# 5_RK3588_OSC_PLL_PMUIO1.net
KiCad netlist of a schematic drawn in Altium Designer
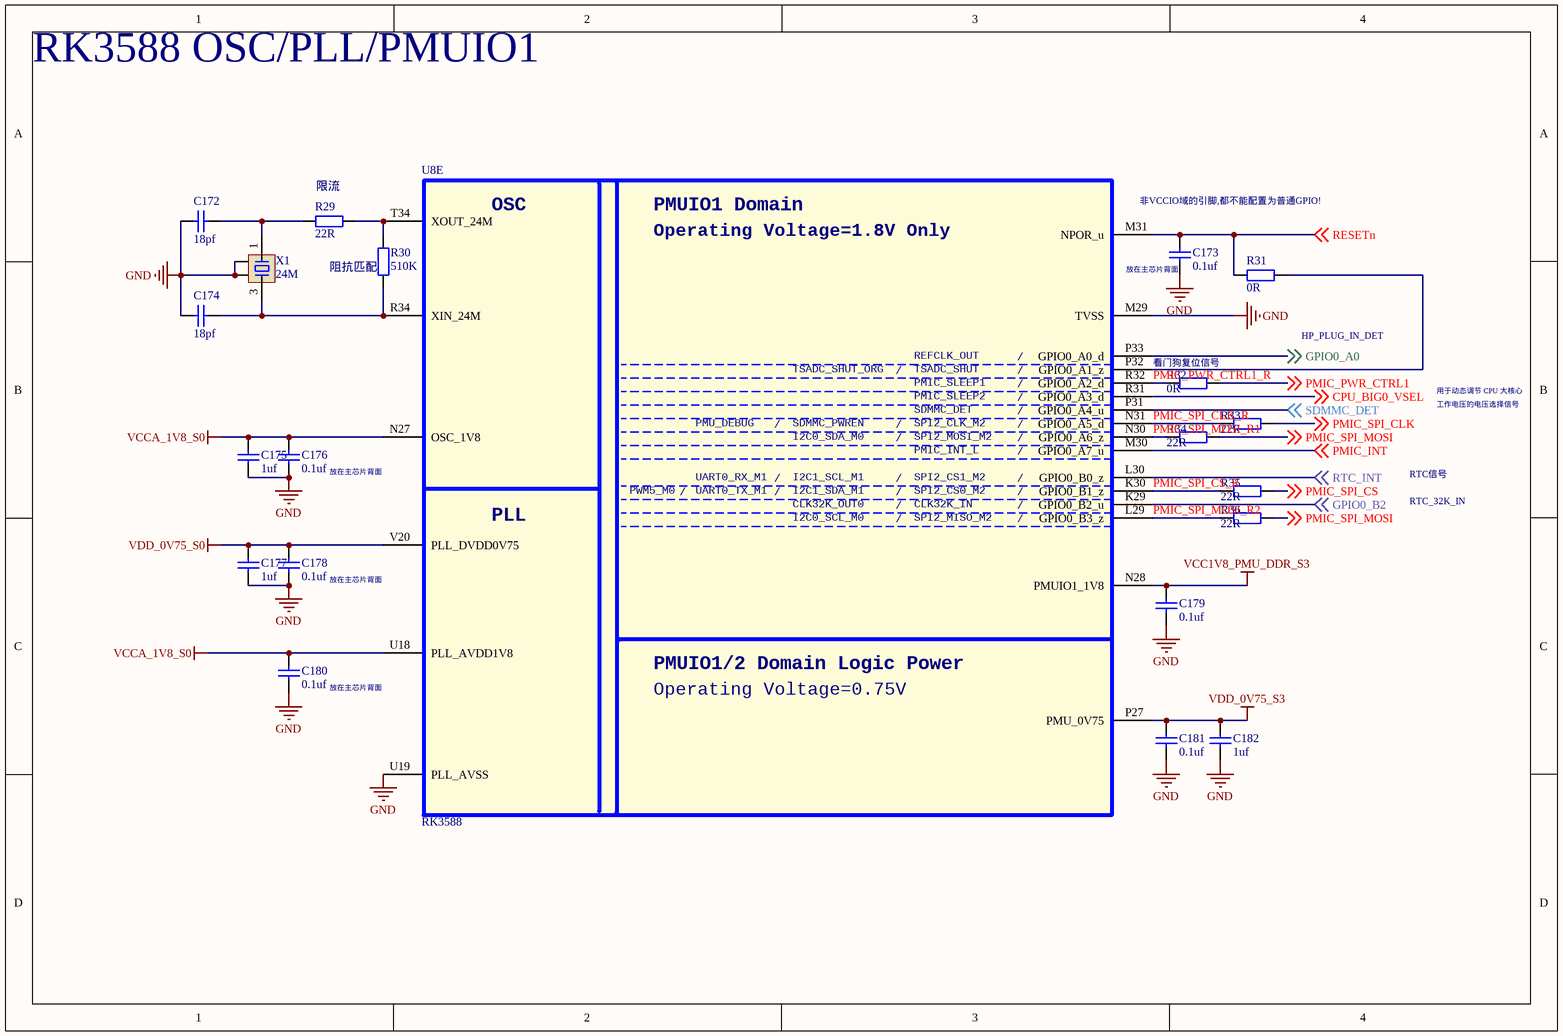
[diagram p0: 5.RK3588_OSC_PLL_PMUIO1.SchDoc]

(export (version "E")
  (design (tool "Eeschema 10.0.6"))
  (components
    (comp (ref "C172")
      (value "18pf")
      (footprint "0.PCB1:C0402_L")
      (description "贴片电容/MLCC电容")
      (libsource (lib "RK3588") (part "C"))
    )
    (comp (ref "C173")
      (value "0.1uf")
      (footprint "0.PCB1:C0201_L")
      (description "贴片电容/MLCC电容")
      (libsource (lib "RK3588") (part "C"))
    )
    (comp (ref "C174")
      (value "18pf")
      (footprint "0.PCB1:C0402_L")
      (description "贴片电容/MLCC电容")
      (libsource (lib "RK3588") (part "C"))
    )
    (comp (ref "C175")
      (value "1uf")
      (footprint "0.PCB1:C0201_L")
      (description "贴片电容/MLCC电容")
      (libsource (lib "RK3588") (part "C"))
    )
    (comp (ref "C176")
      (value "0.1uf")
      (footprint "0.PCB1:C0201_L")
      (description "贴片电容/MLCC电容")
      (libsource (lib "RK3588") (part "C"))
    )
    (comp (ref "C177")
      (value "1uf")
      (footprint "0.PCB1:C0201_L")
      (description "贴片电容/MLCC电容")
      (libsource (lib "RK3588") (part "C"))
    )
    (comp (ref "C178")
      (value "0.1uf")
      (footprint "0.PCB1:C0201_L")
      (description "贴片电容/MLCC电容")
      (libsource (lib "RK3588") (part "C"))
    )
    (comp (ref "C179")
      (value "0.1uf")
      (footprint "0.PCB1:C0201_L")
      (description "贴片电容/MLCC电容")
      (libsource (lib "RK3588") (part "C"))
    )
    (comp (ref "C180")
      (value "0.1uf")
      (footprint "0.PCB1:C0201_L")
      (description "贴片电容/MLCC电容")
      (libsource (lib "RK3588") (part "C"))
    )
    (comp (ref "C181")
      (value "0.1uf")
      (footprint "0.PCB1:C0201_L")
      (description "贴片电容/MLCC电容")
      (libsource (lib "RK3588") (part "C"))
    )
    (comp (ref "C182")
      (value "1uf")
      (footprint "0.PCB1:C0201_L")
      (description "贴片电容/MLCC电容")
      (libsource (lib "RK3588") (part "C"))
    )
    (comp (ref "R29")
      (value "22R")
      (footprint "0.PCB1:R0402_L")
      (description "贴片电阻")
      (libsource (lib "RK3588") (part "R"))
    )
    (comp (ref "R30")
      (value "510K")
      (footprint "0.PCB1:R0402_L")
      (description "贴片电阻")
      (libsource (lib "RK3588") (part "R"))
    )
    (comp (ref "R31")
      (value "0R")
      (footprint "0.PCB1:R0201_L")
      (description "贴片电阻")
      (libsource (lib "RK3588") (part "R"))
    )
    (comp (ref "R32")
      (value "0R")
      (footprint "0.PCB1:R0201_L")
      (description "贴片电阻")
      (libsource (lib "RK3588") (part "R"))
    )
    (comp (ref "R33")
      (value "22R")
      (footprint "0.PCB1:R0201_L")
      (description "贴片电阻")
      (libsource (lib "RK3588") (part "R"))
    )
    (comp (ref "R34")
      (value "22R")
      (footprint "0.PCB1:R0201_L")
      (description "贴片电阻")
      (libsource (lib "RK3588") (part "R"))
    )
    (comp (ref "R35")
      (value "22R")
      (footprint "0.PCB1:R0201_L")
      (description "贴片电阻")
      (libsource (lib "RK3588") (part "R"))
    )
    (comp (ref "R36")
      (value "22R")
      (footprint "0.PCB1:R0201_L")
      (description "贴片电阻")
      (libsource (lib "RK3588") (part "R"))
    )
    (comp (ref "U8")
      (value "RK3588")
      (footprint "0.PCB1:BGA1088_23R00X23R00X2R00")
      (description "ROCKCHIP SOC")
      (libsource (lib "RK3588") (part "SOC_RK3588"))
    )
    (comp (ref "X1")
      (value "24M")
      (footprint "0.PCB1:XTAL-3225-4P")
      (description "4脚无源晶振(谐振器）")
      (libsource (lib "RK3588") (part "XTAL-4P"))
    )
  )
  (nets
    (net (code "1") (name "/PMIC_PWR_CTRL1_R") (class "Default")
      (node (ref "R32") (pin "1") (pinfunction "1_1") (pintype "passive"))
      (node (ref "U8") (pin "R32") (pinfunction "GPIO0_A2_d_R32") (pintype "passive"))
    )
    (net (code "2") (name "/PMIC_SPI_CLK_R") (class "Default")
      (node (ref "R33") (pin "1") (pinfunction "1_1") (pintype "passive"))
      (node (ref "U8") (pin "N31") (pinfunction "GPIO0_A5_d_N31") (pintype "passive"))
    )
    (net (code "3") (name "/PMIC_SPI_CS_R") (class "Default")
      (node (ref "R35") (pin "1") (pinfunction "1_1") (pintype "passive"))
      (node (ref "U8") (pin "K30") (pinfunction "GPIO0_B1_z_K30") (pintype "passive"))
    )
    (net (code "4") (name "/PMIC_SPI_MOSI_R1") (class "Default")
      (node (ref "R34") (pin "1") (pinfunction "1_1") (pintype "passive"))
      (node (ref "U8") (pin "N30") (pinfunction "GPIO0_A6_z_N30") (pintype "passive"))
    )
    (net (code "5") (name "/PMIC_SPI_MOSI_R2") (class "Default")
      (node (ref "R36") (pin "1") (pinfunction "1_1") (pintype "passive"))
      (node (ref "U8") (pin "L29") (pinfunction "GPIO0_B3_z_L29") (pintype "passive"))
    )
    (net (code "6") (name "CPU_BIG0_VSEL") (class "Default")
      (node (ref "U8") (pin "R31") (pinfunction "GPIO0_A3_d_R31") (pintype "passive"))
    )
    (net (code "7") (name "GND") (class "Default")
      (node (ref "C172") (pin "1") (pinfunction "1_1") (pintype "passive"))
      (node (ref "C173") (pin "1") (pinfunction "1_1") (pintype "passive"))
      (node (ref "C174") (pin "1") (pinfunction "1_1") (pintype "passive"))
      (node (ref "C175") (pin "1") (pinfunction "1_1") (pintype "passive"))
      (node (ref "C176") (pin "1") (pinfunction "1_1") (pintype "passive"))
      (node (ref "C177") (pin "1") (pinfunction "1_1") (pintype "passive"))
      (node (ref "C178") (pin "1") (pinfunction "1_1") (pintype "passive"))
      (node (ref "C179") (pin "1") (pinfunction "1_1") (pintype "passive"))
      (node (ref "C180") (pin "1") (pinfunction "1_1") (pintype "passive"))
      (node (ref "C181") (pin "1") (pinfunction "1_1") (pintype "passive"))
      (node (ref "C182") (pin "1") (pinfunction "1_1") (pintype "passive"))
      (node (ref "U8") (pin "M29") (pinfunction "TVSS_M29") (pintype "power_in"))
      (node (ref "U8") (pin "U19") (pinfunction "PLL_AVSS_U19") (pintype "power_in"))
      (node (ref "X1") (pin "2") (pinfunction "2_2") (pintype "passive"))
      (node (ref "X1") (pin "4") (pinfunction "4_4") (pintype "passive"))
    )
    (net (code "8") (name "GPIO0_A0") (class "Default")
      (node (ref "U8") (pin "P33") (pinfunction "GPIO0_A0_d_P33") (pintype "passive"))
    )
    (net (code "9") (name "GPIO0_B2") (class "Default")
      (node (ref "U8") (pin "K29") (pinfunction "GPIO0_B2_u_K29") (pintype "passive"))
    )
    (net (code "10") (name "Net-(C172-Pad2)") (class "Default")
      (node (ref "C172") (pin "2") (pinfunction "2_2") (pintype "passive"))
      (node (ref "R29") (pin "2") (pinfunction "2_2") (pintype "passive"))
      (node (ref "X1") (pin "1") (pinfunction "1_1") (pintype "passive"))
    )
    (net (code "11") (name "Net-(U8E-GPIO0_A1_z)") (class "Default")
      (node (ref "R31") (pin "2") (pinfunction "2_2") (pintype "passive"))
      (node (ref "U8") (pin "P32") (pinfunction "GPIO0_A1_z_P32") (pintype "passive"))
    )
    (net (code "12") (name "Net-(U8E-XIN_24M)") (class "Default")
      (node (ref "C174") (pin "2") (pinfunction "2_2") (pintype "passive"))
      (node (ref "R30") (pin "1") (pinfunction "1_1") (pintype "passive"))
      (node (ref "U8") (pin "R34") (pinfunction "XIN_24M_R34") (pintype "passive"))
      (node (ref "X1") (pin "3") (pinfunction "3_3") (pintype "passive"))
    )
    (net (code "13") (name "Net-(U8E-XOUT_24M)") (class "Default")
      (node (ref "R29") (pin "1") (pinfunction "1_1") (pintype "passive"))
      (node (ref "R30") (pin "2") (pinfunction "2_2") (pintype "passive"))
      (node (ref "U8") (pin "T34") (pinfunction "XOUT_24M_T34") (pintype "passive"))
    )
    (net (code "14") (name "PMIC_INT") (class "Default")
      (node (ref "U8") (pin "M30") (pinfunction "GPIO0_A7_u_M30") (pintype "passive"))
    )
    (net (code "15") (name "PMIC_PWR_CTRL1") (class "Default")
      (node (ref "R32") (pin "2") (pinfunction "2_2") (pintype "passive"))
    )
    (net (code "16") (name "PMIC_SPI_CLK") (class "Default")
      (node (ref "R33") (pin "2") (pinfunction "2_2") (pintype "passive"))
    )
    (net (code "17") (name "PMIC_SPI_CS") (class "Default")
      (node (ref "R35") (pin "2") (pinfunction "2_2") (pintype "passive"))
    )
    (net (code "18") (name "PMIC_SPI_MOSI") (class "Default")
      (node (ref "R34") (pin "2") (pinfunction "2_2") (pintype "passive"))
      (node (ref "R36") (pin "2") (pinfunction "2_2") (pintype "passive"))
    )
    (net (code "19") (name "RESETn") (class "Default")
      (node (ref "C173") (pin "2") (pinfunction "2_2") (pintype "passive"))
      (node (ref "R31") (pin "1") (pinfunction "1_1") (pintype "passive"))
      (node (ref "U8") (pin "M31") (pinfunction "NPOR_u_M31") (pintype "passive"))
    )
    (net (code "20") (name "RTC_INT") (class "Default")
      (node (ref "U8") (pin "L30") (pinfunction "GPIO0_B0_z_L30") (pintype "passive"))
    )
    (net (code "21") (name "SDMMC_DET") (class "Default")
      (node (ref "U8") (pin "P31") (pinfunction "GPIO0_A4_u_P31") (pintype "passive"))
    )
    (net (code "22") (name "VCC1V8_PMU_DDR_S3") (class "Default")
      (node (ref "C179") (pin "2") (pinfunction "2_2") (pintype "passive"))
      (node (ref "U8") (pin "N28") (pinfunction "PMUIO1_1V8_N28") (pintype "power_in"))
    )
    (net (code "23") (name "VCCA_1V8_S0") (class "Default")
      (node (ref "C175") (pin "2") (pinfunction "2_2") (pintype "passive"))
      (node (ref "C176") (pin "2") (pinfunction "2_2") (pintype "passive"))
      (node (ref "C180") (pin "2") (pinfunction "2_2") (pintype "passive"))
      (node (ref "U8") (pin "N27") (pinfunction "OSC_1V8_N27") (pintype "power_in"))
      (node (ref "U8") (pin "U18") (pinfunction "PLL_AVDD1V8_U18") (pintype "power_in"))
    )
    (net (code "24") (name "VDD_0V75_S0") (class "Default")
      (node (ref "C177") (pin "2") (pinfunction "2_2") (pintype "passive"))
      (node (ref "C178") (pin "2") (pinfunction "2_2") (pintype "passive"))
      (node (ref "U8") (pin "V20") (pinfunction "PLL_DVDD0V75_V20") (pintype "power_in"))
    )
    (net (code "25") (name "VDD_0V75_S3") (class "Default")
      (node (ref "C181") (pin "2") (pinfunction "2_2") (pintype "passive"))
      (node (ref "C182") (pin "2") (pinfunction "2_2") (pintype "passive"))
      (node (ref "U8") (pin "P27") (pinfunction "PMU_0V75_P27") (pintype "power_in"))
    )
  )
)
